# met.net
KiCad netlist of a schematic drawn in EAGLE
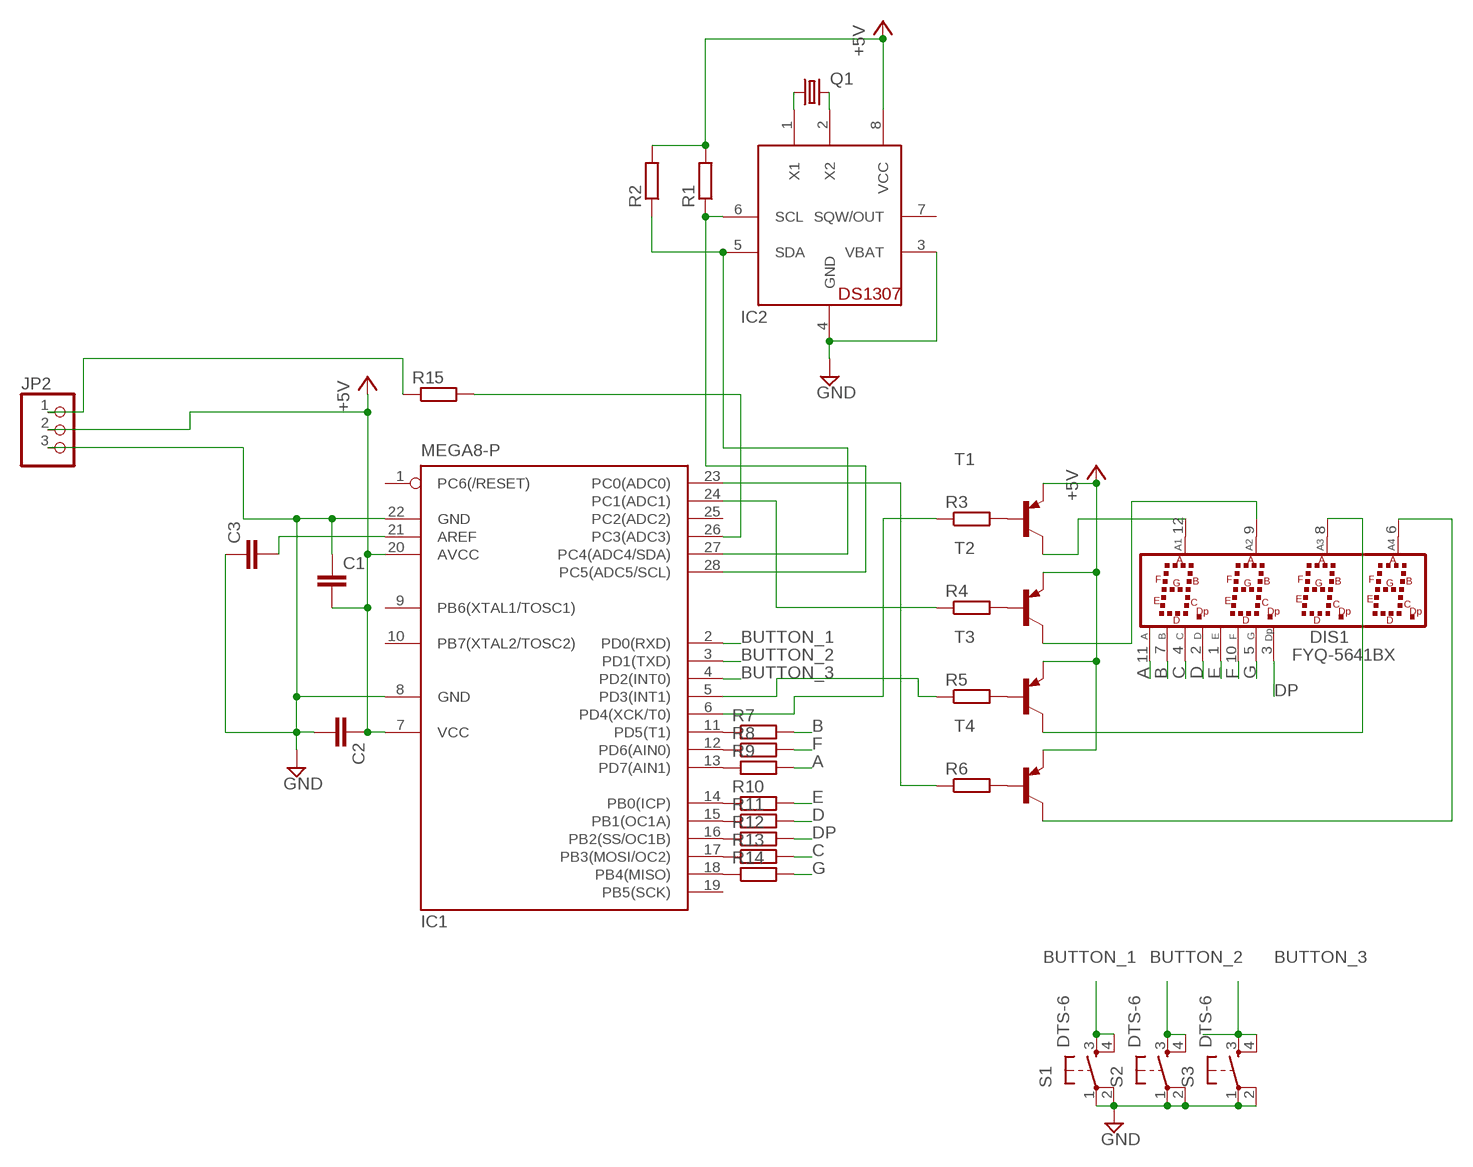
[diagram p0: schematic, sheet 1]

(export (version "E")
  (design (tool "Eeschema 10.0.6"))
  (components
    (comp (ref "C1")
      (value "C-EU025-024X044")
      (footprint "eagle-import:C025-024X044")
      (libsource (lib "eagle-import") (part "C-EU025-024X044"))
    )
    (comp (ref "C2")
      (value "C-EU025-024X044")
      (footprint "eagle-import:C025-024X044")
      (libsource (lib "eagle-import") (part "C-EU025-024X044"))
    )
    (comp (ref "C3")
      (value "C-EU025-024X044")
      (footprint "eagle-import:C025-024X044")
      (libsource (lib "eagle-import") (part "C-EU025-024X044"))
    )
    (comp (ref "DIS1")
      (value "FYQ-5641BX")
      (footprint "eagle-import:FYQ5641")
      (libsource (lib "eagle-import") (part "FYQ-5641BX"))
    )
    (comp (ref "IC1")
      (value "MEGA8-P")
      (footprint "eagle-import:DIL28-3")
      (libsource (lib "eagle-import") (part "MEGA8-P"))
    )
    (comp (ref "IC2")
      (value "DS1307")
      (footprint "eagle-import:DIL08")
      (libsource (lib "eagle-import") (part "DS1307"))
    )
    (comp (ref "JP2")
      (value "PINHD-1X3")
      (footprint "eagle-import:1X03")
      (libsource (lib "eagle-import") (part "PINHD-1X3"))
    )
    (comp (ref "Q1")
      (value "CRYSTALTC26V")
      (footprint "eagle-import:TC26V")
      (libsource (lib "eagle-import") (part "CRYSTALTC26V"))
    )
    (comp (ref "R1")
      (value "R-EU_0207/2V")
      (footprint "eagle-import:0207_2V")
      (libsource (lib "eagle-import") (part "R-EU_0207/2V"))
    )
    (comp (ref "R2")
      (value "R-EU_0207/2V")
      (footprint "eagle-import:0207_2V")
      (libsource (lib "eagle-import") (part "R-EU_0207/2V"))
    )
    (comp (ref "R3")
      (value "R-EU_0204/2V")
      (footprint "eagle-import:0204V")
      (libsource (lib "eagle-import") (part "R-EU_0204/2V"))
    )
    (comp (ref "R4")
      (value "R-EU_0204/2V")
      (footprint "eagle-import:0204V")
      (libsource (lib "eagle-import") (part "R-EU_0204/2V"))
    )
    (comp (ref "R5")
      (value "R-EU_0204/2V")
      (footprint "eagle-import:0204V")
      (libsource (lib "eagle-import") (part "R-EU_0204/2V"))
    )
    (comp (ref "R6")
      (value "R-EU_0204/2V")
      (footprint "eagle-import:0204V")
      (libsource (lib "eagle-import") (part "R-EU_0204/2V"))
    )
    (comp (ref "R7")
      (value "R-EU_0204/2V")
      (footprint "eagle-import:0204V")
      (libsource (lib "eagle-import") (part "R-EU_0204/2V"))
    )
    (comp (ref "R8")
      (value "R-EU_0204/2V")
      (footprint "eagle-import:0204V")
      (libsource (lib "eagle-import") (part "R-EU_0204/2V"))
    )
    (comp (ref "R9")
      (value "R-EU_0204/2V")
      (footprint "eagle-import:0204V")
      (libsource (lib "eagle-import") (part "R-EU_0204/2V"))
    )
    (comp (ref "R10")
      (value "R-EU_0204/2V")
      (footprint "eagle-import:0204V")
      (libsource (lib "eagle-import") (part "R-EU_0204/2V"))
    )
    (comp (ref "R11")
      (value "R-EU_0204/2V")
      (footprint "eagle-import:0204V")
      (libsource (lib "eagle-import") (part "R-EU_0204/2V"))
    )
    (comp (ref "R12")
      (value "R-EU_0204/2V")
      (footprint "eagle-import:0204V")
      (libsource (lib "eagle-import") (part "R-EU_0204/2V"))
    )
    (comp (ref "R13")
      (value "R-EU_0204/2V")
      (footprint "eagle-import:0204V")
      (libsource (lib "eagle-import") (part "R-EU_0204/2V"))
    )
    (comp (ref "R14")
      (value "R-EU_0204/2V")
      (footprint "eagle-import:0204V")
      (libsource (lib "eagle-import") (part "R-EU_0204/2V"))
    )
    (comp (ref "R15")
      (value "R-EU_0204/2V")
      (footprint "eagle-import:0204V")
      (libsource (lib "eagle-import") (part "R-EU_0204/2V"))
    )
    (comp (ref "S1")
      (value "DTS-6")
      (footprint "eagle-import:DTS-6")
      (libsource (lib "eagle-import") (part "DTS-6"))
    )
    (comp (ref "S2")
      (value "DTS-6")
      (footprint "eagle-import:DTS-6")
      (libsource (lib "eagle-import") (part "DTS-6"))
    )
    (comp (ref "S3")
      (value "DTS-6")
      (footprint "eagle-import:DTS-6")
      (libsource (lib "eagle-import") (part "DTS-6"))
    )
    (comp (ref "T1")
      (value "BC327-PNP-TO92-EBC")
      (footprint "eagle-import:TO92-EBC")
      (libsource (lib "eagle-import") (part "-PNP-TO92-EBCBC327"))
    )
    (comp (ref "T2")
      (value "BC327-PNP-TO92-EBC")
      (footprint "eagle-import:TO92-EBC")
      (libsource (lib "eagle-import") (part "-PNP-TO92-EBCBC327"))
    )
    (comp (ref "T3")
      (value "BC327-PNP-TO92-EBC")
      (footprint "eagle-import:TO92-EBC")
      (libsource (lib "eagle-import") (part "-PNP-TO92-EBCBC327"))
    )
    (comp (ref "T4")
      (value "BC327-PNP-TO92-EBC")
      (footprint "eagle-import:TO92-EBC")
      (libsource (lib "eagle-import") (part "-PNP-TO92-EBCBC327"))
    )
  )
  (nets
    (net (code "1") (name "+5V") (class "Default")
      (node (ref "C1") (pin "2") (pinfunction "2_2") (pintype "passive"))
      (node (ref "C2") (pin "1") (pinfunction "1_1") (pintype "passive"))
      (node (ref "IC1") (pin "20") (pinfunction "AVCC_20") (pintype "power_in"))
      (node (ref "IC1") (pin "7") (pinfunction "VCC_7") (pintype "power_in"))
      (node (ref "IC2") (pin "8") (pinfunction "VCC_8") (pintype "power_in"))
      (node (ref "JP2") (pin "2") (pinfunction "2_2") (pintype "passive"))
      (node (ref "R1") (pin "2") (pinfunction "2_2") (pintype "passive"))
      (node (ref "R2") (pin "2") (pinfunction "2_2") (pintype "passive"))
      (node (ref "T1") (pin "E") (pinfunction "E_E") (pintype "passive"))
      (node (ref "T2") (pin "E") (pinfunction "E_E") (pintype "passive"))
      (node (ref "T3") (pin "E") (pinfunction "E_E") (pintype "passive"))
      (node (ref "T4") (pin "E") (pinfunction "E_E") (pintype "passive"))
    )
    (net (code "2") (name "/A") (class "Default")
      (node (ref "DIS1") (pin "11") (pinfunction "A_11") (pintype "passive"))
      (node (ref "R9") (pin "2") (pinfunction "2_2") (pintype "passive"))
    )
    (net (code "3") (name "/B") (class "Default")
      (node (ref "DIS1") (pin "7") (pinfunction "B_7") (pintype "passive"))
      (node (ref "R7") (pin "2") (pinfunction "2_2") (pintype "passive"))
    )
    (net (code "4") (name "/BUTTON_1") (class "Default")
      (node (ref "IC1") (pin "2") (pinfunction "PD0(RXD)_2") (pintype "bidirectional"))
      (node (ref "S1") (pin "3") (pinfunction "3_3") (pintype "passive"))
      (node (ref "S1") (pin "4") (pinfunction "4_4") (pintype "passive"))
    )
    (net (code "5") (name "/BUTTON_2") (class "Default")
      (node (ref "IC1") (pin "3") (pinfunction "PD1(TXD)_3") (pintype "bidirectional"))
      (node (ref "S2") (pin "3") (pinfunction "3_3") (pintype "passive"))
      (node (ref "S2") (pin "4") (pinfunction "4_4") (pintype "passive"))
    )
    (net (code "6") (name "/BUTTON_3") (class "Default")
      (node (ref "IC1") (pin "4") (pinfunction "PD2(INT0)_4") (pintype "bidirectional"))
      (node (ref "S3") (pin "3") (pinfunction "3_3") (pintype "passive"))
      (node (ref "S3") (pin "4") (pinfunction "4_4") (pintype "passive"))
    )
    (net (code "7") (name "/C") (class "Default")
      (node (ref "DIS1") (pin "4") (pinfunction "C_4") (pintype "passive"))
      (node (ref "R13") (pin "2") (pinfunction "2_2") (pintype "passive"))
    )
    (net (code "8") (name "/D") (class "Default")
      (node (ref "DIS1") (pin "2") (pinfunction "D_2") (pintype "passive"))
      (node (ref "R11") (pin "2") (pinfunction "2_2") (pintype "passive"))
    )
    (net (code "9") (name "/DP") (class "Default")
      (node (ref "DIS1") (pin "3") (pinfunction "DP_3") (pintype "passive"))
      (node (ref "R12") (pin "2") (pinfunction "2_2") (pintype "passive"))
    )
    (net (code "10") (name "/E") (class "Default")
      (node (ref "DIS1") (pin "1") (pinfunction "E_1") (pintype "passive"))
      (node (ref "R10") (pin "2") (pinfunction "2_2") (pintype "passive"))
    )
    (net (code "11") (name "/F") (class "Default")
      (node (ref "DIS1") (pin "10") (pinfunction "F_10") (pintype "passive"))
      (node (ref "R8") (pin "2") (pinfunction "2_2") (pintype "passive"))
    )
    (net (code "12") (name "/G") (class "Default")
      (node (ref "DIS1") (pin "5") (pinfunction "G_5") (pintype "passive"))
      (node (ref "R14") (pin "2") (pinfunction "2_2") (pintype "passive"))
    )
    (net (code "13") (name "GND") (class "Default")
      (node (ref "C1") (pin "1") (pinfunction "1_1") (pintype "passive"))
      (node (ref "C2") (pin "2") (pinfunction "2_2") (pintype "passive"))
      (node (ref "C3") (pin "1") (pinfunction "1_1") (pintype "passive"))
      (node (ref "IC1") (pin "22") (pinfunction "GND_22") (pintype "power_in"))
      (node (ref "IC1") (pin "8") (pinfunction "GND_8") (pintype "power_in"))
      (node (ref "IC2") (pin "3") (pinfunction "VBAT_3") (pintype "power_in"))
      (node (ref "IC2") (pin "4") (pinfunction "GND_4") (pintype "power_in"))
      (node (ref "JP2") (pin "3") (pinfunction "3_3") (pintype "passive"))
      (node (ref "S1") (pin "1") (pinfunction "1_1") (pintype "passive"))
      (node (ref "S1") (pin "2") (pinfunction "2_2") (pintype "passive"))
      (node (ref "S2") (pin "1") (pinfunction "1_1") (pintype "passive"))
      (node (ref "S2") (pin "2") (pinfunction "2_2") (pintype "passive"))
      (node (ref "S3") (pin "1") (pinfunction "1_1") (pintype "passive"))
      (node (ref "S3") (pin "2") (pinfunction "2_2") (pintype "passive"))
    )
    (net (code "14") (name "Net-(DIS1-A1)") (class "Default")
      (node (ref "DIS1") (pin "12") (pinfunction "A1_12") (pintype "passive"))
      (node (ref "T1") (pin "C") (pinfunction "C_C") (pintype "passive"))
    )
    (net (code "15") (name "Net-(DIS1-A2)") (class "Default")
      (node (ref "DIS1") (pin "9") (pinfunction "A2_9") (pintype "passive"))
      (node (ref "T2") (pin "C") (pinfunction "C_C") (pintype "passive"))
    )
    (net (code "16") (name "Net-(DIS1-A3)") (class "Default")
      (node (ref "DIS1") (pin "8") (pinfunction "A3_8") (pintype "passive"))
      (node (ref "T3") (pin "C") (pinfunction "C_C") (pintype "passive"))
    )
    (net (code "17") (name "Net-(DIS1-A4)") (class "Default")
      (node (ref "DIS1") (pin "6") (pinfunction "A4_6") (pintype "passive"))
      (node (ref "T4") (pin "C") (pinfunction "C_C") (pintype "passive"))
    )
    (net (code "18") (name "Net-(IC1-AREF)") (class "Default")
      (node (ref "C3") (pin "2") (pinfunction "2_2") (pintype "passive"))
      (node (ref "IC1") (pin "21") (pinfunction "AREF_21") (pintype "passive"))
    )
    (net (code "19") (name "Net-(IC1-PB0(ICP))") (class "Default")
      (node (ref "IC1") (pin "14") (pinfunction "PB0(ICP)_14") (pintype "bidirectional"))
      (node (ref "R10") (pin "1") (pinfunction "1_1") (pintype "passive"))
    )
    (net (code "20") (name "Net-(IC1-PB1(OC1A))") (class "Default")
      (node (ref "IC1") (pin "15") (pinfunction "PB1(OC1A)_15") (pintype "bidirectional"))
      (node (ref "R11") (pin "1") (pinfunction "1_1") (pintype "passive"))
    )
    (net (code "21") (name "Net-(IC1-PB2(SS{slash}OC1B))") (class "Default")
      (node (ref "IC1") (pin "16") (pinfunction "PB2(SS/OC1B)_16") (pintype "bidirectional"))
      (node (ref "R12") (pin "1") (pinfunction "1_1") (pintype "passive"))
    )
    (net (code "22") (name "Net-(IC1-PB3(MOSI{slash}OC2))") (class "Default")
      (node (ref "IC1") (pin "17") (pinfunction "PB3(MOSI/OC2)_17") (pintype "bidirectional"))
      (node (ref "R13") (pin "1") (pinfunction "1_1") (pintype "passive"))
    )
    (net (code "23") (name "Net-(IC1-PB4(MISO))") (class "Default")
      (node (ref "IC1") (pin "18") (pinfunction "PB4(MISO)_18") (pintype "bidirectional"))
      (node (ref "R14") (pin "1") (pinfunction "1_1") (pintype "passive"))
    )
    (net (code "24") (name "Net-(IC1-PC0(ADC0))") (class "Default")
      (node (ref "IC1") (pin "23") (pinfunction "PC0(ADC0)_23") (pintype "bidirectional"))
      (node (ref "R6") (pin "1") (pinfunction "1_1") (pintype "passive"))
    )
    (net (code "25") (name "Net-(IC1-PC1(ADC1))") (class "Default")
      (node (ref "IC1") (pin "24") (pinfunction "PC1(ADC1)_24") (pintype "bidirectional"))
      (node (ref "R4") (pin "1") (pinfunction "1_1") (pintype "passive"))
    )
    (net (code "26") (name "Net-(IC1-PC3(ADC3))") (class "Default")
      (node (ref "IC1") (pin "26") (pinfunction "PC3(ADC3)_26") (pintype "bidirectional"))
      (node (ref "R15") (pin "2") (pinfunction "2_2") (pintype "passive"))
    )
    (net (code "27") (name "Net-(IC1-PC4(ADC4{slash}SDA))") (class "Default")
      (node (ref "IC1") (pin "27") (pinfunction "PC4(ADC4/SDA)_27") (pintype "bidirectional"))
      (node (ref "IC2") (pin "5") (pinfunction "SDA_5") (pintype "bidirectional"))
      (node (ref "R2") (pin "1") (pinfunction "1_1") (pintype "passive"))
    )
    (net (code "28") (name "Net-(IC1-PC5(ADC5{slash}SCL))") (class "Default")
      (node (ref "IC1") (pin "28") (pinfunction "PC5(ADC5/SCL)_28") (pintype "bidirectional"))
      (node (ref "IC2") (pin "6") (pinfunction "SCL_6") (pintype "bidirectional"))
      (node (ref "R1") (pin "1") (pinfunction "1_1") (pintype "passive"))
    )
    (net (code "29") (name "Net-(IC1-PD3(INT1))") (class "Default")
      (node (ref "IC1") (pin "5") (pinfunction "PD3(INT1)_5") (pintype "bidirectional"))
      (node (ref "R5") (pin "1") (pinfunction "1_1") (pintype "passive"))
    )
    (net (code "30") (name "Net-(IC1-PD4(XCK{slash}T0))") (class "Default")
      (node (ref "IC1") (pin "6") (pinfunction "PD4(XCK/T0)_6") (pintype "bidirectional"))
      (node (ref "R3") (pin "1") (pinfunction "1_1") (pintype "passive"))
    )
    (net (code "31") (name "Net-(IC1-PD5(T1))") (class "Default")
      (node (ref "IC1") (pin "11") (pinfunction "PD5(T1)_11") (pintype "bidirectional"))
      (node (ref "R7") (pin "1") (pinfunction "1_1") (pintype "passive"))
    )
    (net (code "32") (name "Net-(IC1-PD6(AIN0))") (class "Default")
      (node (ref "IC1") (pin "12") (pinfunction "PD6(AIN0)_12") (pintype "bidirectional"))
      (node (ref "R8") (pin "1") (pinfunction "1_1") (pintype "passive"))
    )
    (net (code "33") (name "Net-(IC1-PD7(AIN1))") (class "Default")
      (node (ref "IC1") (pin "13") (pinfunction "PD7(AIN1)_13") (pintype "bidirectional"))
      (node (ref "R9") (pin "1") (pinfunction "1_1") (pintype "passive"))
    )
    (net (code "34") (name "Net-(IC2-X1)") (class "Default")
      (node (ref "IC2") (pin "1") (pinfunction "X1_1") (pintype "passive"))
      (node (ref "Q1") (pin "1") (pinfunction "1_1") (pintype "passive"))
    )
    (net (code "35") (name "Net-(IC2-X2)") (class "Default")
      (node (ref "IC2") (pin "2") (pinfunction "X2_2") (pintype "passive"))
      (node (ref "Q1") (pin "2") (pinfunction "2_2") (pintype "passive"))
    )
    (net (code "36") (name "Net-(JP2-Pad1)") (class "Default")
      (node (ref "JP2") (pin "1") (pinfunction "1_1") (pintype "passive"))
      (node (ref "R15") (pin "1") (pinfunction "1_1") (pintype "passive"))
    )
    (net (code "37") (name "Net-(R3-Pad2)") (class "Default")
      (node (ref "R3") (pin "2") (pinfunction "2_2") (pintype "passive"))
      (node (ref "T1") (pin "B") (pinfunction "B_B") (pintype "passive"))
    )
    (net (code "38") (name "Net-(R4-Pad2)") (class "Default")
      (node (ref "R4") (pin "2") (pinfunction "2_2") (pintype "passive"))
      (node (ref "T2") (pin "B") (pinfunction "B_B") (pintype "passive"))
    )
    (net (code "39") (name "Net-(R5-Pad2)") (class "Default")
      (node (ref "R5") (pin "2") (pinfunction "2_2") (pintype "passive"))
      (node (ref "T3") (pin "B") (pinfunction "B_B") (pintype "passive"))
    )
    (net (code "40") (name "Net-(R6-Pad2)") (class "Default")
      (node (ref "R6") (pin "2") (pinfunction "2_2") (pintype "passive"))
      (node (ref "T4") (pin "B") (pinfunction "B_B") (pintype "passive"))
    )
    (net (code "41") (name "unconnected-(IC1-PB5(SCK)-Pad19)") (class "Default")
      (node (ref "IC1") (pin "19") (pinfunction "PB5(SCK)_19") (pintype "bidirectional"))
    )
    (net (code "42") (name "unconnected-(IC1-PB6(XTAL1{slash}TOSC1)-Pad9)") (class "Default")
      (node (ref "IC1") (pin "9") (pinfunction "PB6(XTAL1/TOSC1)_9") (pintype "bidirectional"))
    )
    (net (code "43") (name "unconnected-(IC1-PB7(XTAL2{slash}TOSC2)-Pad10)") (class "Default")
      (node (ref "IC1") (pin "10") (pinfunction "PB7(XTAL2/TOSC2)_10") (pintype "bidirectional"))
    )
    (net (code "44") (name "unconnected-(IC1-PC2(ADC2)-Pad25)") (class "Default")
      (node (ref "IC1") (pin "25") (pinfunction "PC2(ADC2)_25") (pintype "bidirectional"))
    )
    (net (code "45") (name "unconnected-(IC1-PC6({slash}RESET)-Pad1)") (class "Default")
      (node (ref "IC1") (pin "1") (pinfunction "PC6(/RESET)_1") (pintype "bidirectional"))
    )
    (net (code "46") (name "unconnected-(IC2-SQW{slash}OUT-Pad7)") (class "Default")
      (node (ref "IC2") (pin "7") (pinfunction "SQW/OUT_7") (pintype "bidirectional"))
    )
  )
)
